# PQS42019_2_v4.net
KiCad netlist of a schematic drawn in EAGLE
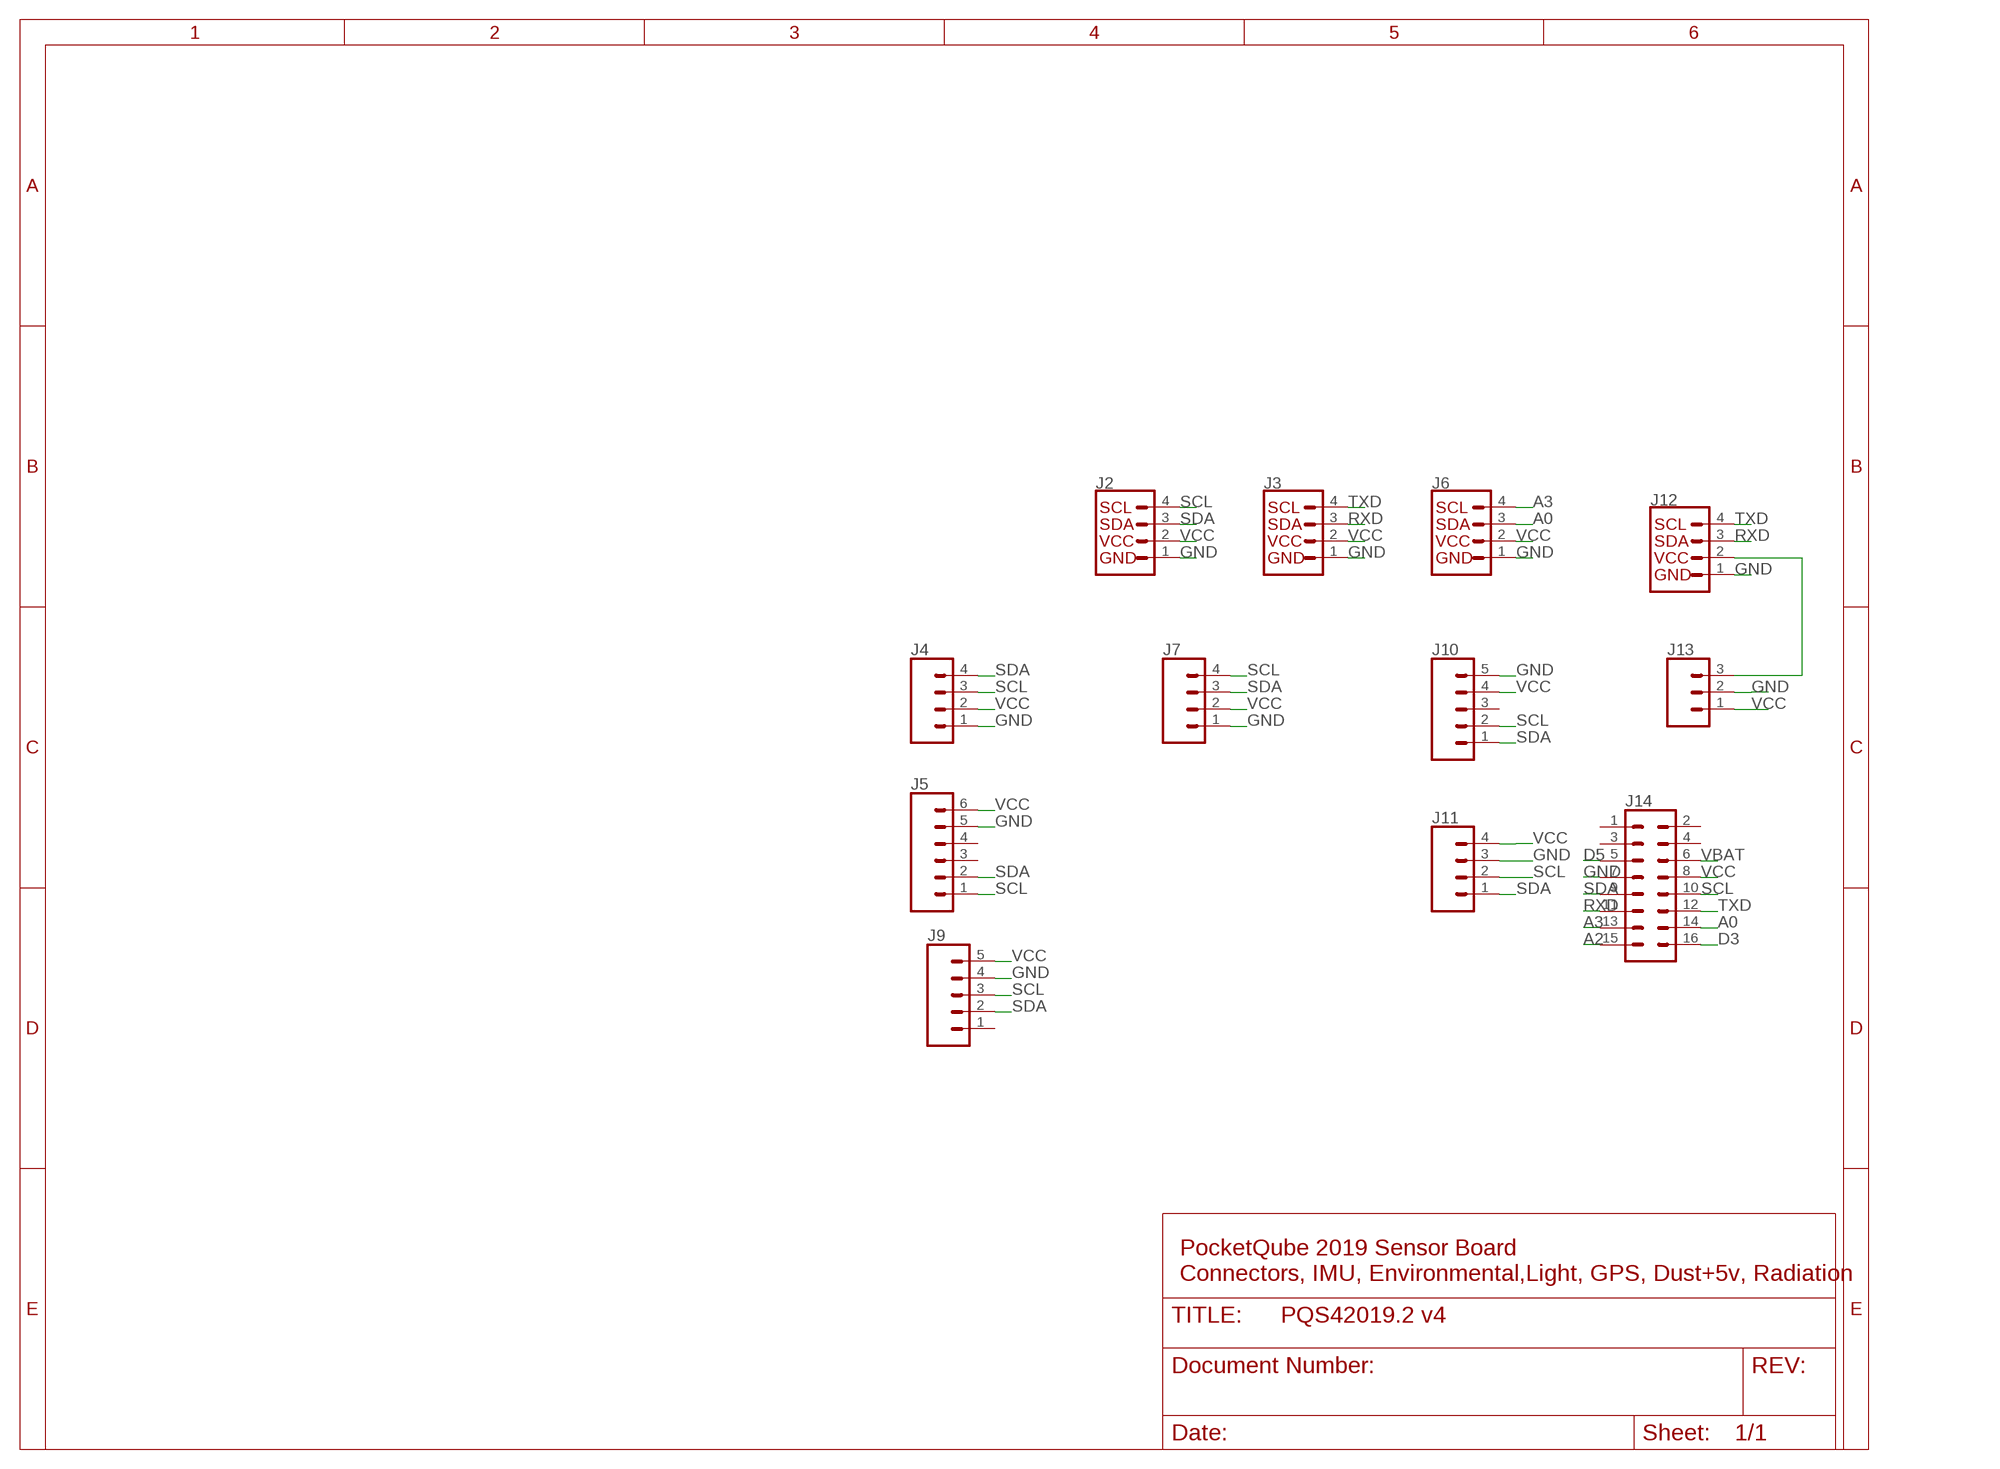
[diagram p0: schematic, sheet 1]

(export (version "E")
  (design (tool "Eeschema 10.0.6"))
  (components
    (comp (ref "J2")
      (value "QWIIC_CONNECTORJS-1MM")
      (footprint "eagle-import:1X04_1MM_RA")
      (libsource (lib "eagle-import") (part "QWIIC_CONNECTORJS-1MM"))
    )
    (comp (ref "J3")
      (value "QWIIC_CONNECTORJS-1MM")
      (footprint "eagle-import:1X04_1MM_RA")
      (libsource (lib "eagle-import") (part "QWIIC_CONNECTORJS-1MM"))
    )
    (comp (ref "J4")
      (value "CONN_04")
      (footprint "eagle-import:1X04")
      (libsource (lib "eagle-import") (part "CONN_04"))
    )
    (comp (ref "J5")
      (value "CONN_06SILK_FEMALE_PTH")
      (footprint "eagle-import:1X06")
      (libsource (lib "eagle-import") (part "CONN_06SILK_FEMALE_PTH"))
    )
    (comp (ref "J6")
      (value "QWIIC_CONNECTORJS-1MM")
      (footprint "eagle-import:1X04_1MM_RA")
      (libsource (lib "eagle-import") (part "QWIIC_CONNECTORJS-1MM"))
    )
    (comp (ref "J7")
      (value "CONN_04")
      (footprint "eagle-import:1X04")
      (libsource (lib "eagle-import") (part "CONN_04"))
    )
    (comp (ref "J9")
      (value "CONN_05")
      (footprint "eagle-import:1X05")
      (libsource (lib "eagle-import") (part "CONN_05"))
    )
    (comp (ref "J10")
      (value "CONN_05")
      (footprint "eagle-import:1X05")
      (libsource (lib "eagle-import") (part "CONN_05"))
    )
    (comp (ref "J11")
      (value "CONN_04")
      (footprint "eagle-import:1X04")
      (libsource (lib "eagle-import") (part "CONN_04"))
    )
    (comp (ref "J12")
      (value "QWIIC_CONNECTORJS-1MM")
      (footprint "eagle-import:1X04_1MM_RA")
      (libsource (lib "eagle-import") (part "QWIIC_CONNECTORJS-1MM"))
    )
    (comp (ref "J13")
      (value "CONN_03")
      (footprint "eagle-import:1X03")
      (libsource (lib "eagle-import") (part "CONN_03"))
    )
    (comp (ref "J14")
      (value "CONN_08X2")
      (footprint "eagle-import:2X8")
      (libsource (lib "eagle-import") (part "CONN_08X2"))
    )
  )
  (nets
    (net (code "1") (name "/A0") (class "Default")
      (node (ref "J14") (pin "14") (pinfunction "14_14") (pintype "passive"))
      (node (ref "J6") (pin "3") (pinfunction "3_3") (pintype "passive"))
    )
    (net (code "2") (name "/A2") (class "Default")
      (node (ref "J14") (pin "15") (pinfunction "15_15") (pintype "passive"))
    )
    (net (code "3") (name "/A3") (class "Default")
      (node (ref "J14") (pin "13") (pinfunction "13_13") (pintype "passive"))
      (node (ref "J6") (pin "4") (pinfunction "4_4") (pintype "passive"))
    )
    (net (code "4") (name "/D3") (class "Default")
      (node (ref "J14") (pin "16") (pinfunction "16_16") (pintype "passive"))
    )
    (net (code "5") (name "/D5") (class "Default")
      (node (ref "J14") (pin "5") (pinfunction "5_5") (pintype "passive"))
    )
    (net (code "6") (name "/GND") (class "Default")
      (node (ref "J10") (pin "5") (pinfunction "5_5") (pintype "passive"))
      (node (ref "J11") (pin "3") (pinfunction "3_3") (pintype "passive"))
      (node (ref "J12") (pin "1") (pinfunction "1_1") (pintype "power_in"))
      (node (ref "J13") (pin "2") (pinfunction "2_2") (pintype "passive"))
      (node (ref "J14") (pin "7") (pinfunction "7_7") (pintype "passive"))
      (node (ref "J2") (pin "1") (pinfunction "1_1") (pintype "power_in"))
      (node (ref "J3") (pin "1") (pinfunction "1_1") (pintype "power_in"))
      (node (ref "J4") (pin "1") (pinfunction "1_1") (pintype "passive"))
      (node (ref "J5") (pin "5") (pinfunction "5_5") (pintype "passive"))
      (node (ref "J6") (pin "1") (pinfunction "1_1") (pintype "power_in"))
      (node (ref "J7") (pin "1") (pinfunction "1_1") (pintype "passive"))
      (node (ref "J9") (pin "4") (pinfunction "4_4") (pintype "passive"))
    )
    (net (code "7") (name "/RXD") (class "Default")
      (node (ref "J12") (pin "3") (pinfunction "3_3") (pintype "passive"))
      (node (ref "J14") (pin "11") (pinfunction "11_11") (pintype "passive"))
      (node (ref "J3") (pin "3") (pinfunction "3_3") (pintype "passive"))
    )
    (net (code "8") (name "/SCL") (class "Default")
      (node (ref "J10") (pin "2") (pinfunction "2_2") (pintype "passive"))
      (node (ref "J11") (pin "2") (pinfunction "2_2") (pintype "passive"))
      (node (ref "J14") (pin "10") (pinfunction "10_10") (pintype "passive"))
      (node (ref "J2") (pin "4") (pinfunction "4_4") (pintype "passive"))
      (node (ref "J4") (pin "3") (pinfunction "3_3") (pintype "passive"))
      (node (ref "J5") (pin "1") (pinfunction "1_1") (pintype "passive"))
      (node (ref "J7") (pin "4") (pinfunction "4_4") (pintype "passive"))
      (node (ref "J9") (pin "3") (pinfunction "3_3") (pintype "passive"))
    )
    (net (code "9") (name "/SDA") (class "Default")
      (node (ref "J10") (pin "1") (pinfunction "1_1") (pintype "passive"))
      (node (ref "J11") (pin "1") (pinfunction "1_1") (pintype "passive"))
      (node (ref "J14") (pin "9") (pinfunction "9_9") (pintype "passive"))
      (node (ref "J2") (pin "3") (pinfunction "3_3") (pintype "passive"))
      (node (ref "J4") (pin "4") (pinfunction "4_4") (pintype "passive"))
      (node (ref "J5") (pin "2") (pinfunction "2_2") (pintype "passive"))
      (node (ref "J7") (pin "3") (pinfunction "3_3") (pintype "passive"))
      (node (ref "J9") (pin "2") (pinfunction "2_2") (pintype "passive"))
    )
    (net (code "10") (name "/TXD") (class "Default")
      (node (ref "J12") (pin "4") (pinfunction "4_4") (pintype "passive"))
      (node (ref "J14") (pin "12") (pinfunction "12_12") (pintype "passive"))
      (node (ref "J3") (pin "4") (pinfunction "4_4") (pintype "passive"))
    )
    (net (code "11") (name "/VBAT") (class "Default")
      (node (ref "J14") (pin "6") (pinfunction "6_6") (pintype "passive"))
    )
    (net (code "12") (name "/VCC") (class "Default")
      (node (ref "J10") (pin "4") (pinfunction "4_4") (pintype "passive"))
      (node (ref "J11") (pin "4") (pinfunction "4_4") (pintype "passive"))
      (node (ref "J13") (pin "1") (pinfunction "1_1") (pintype "passive"))
      (node (ref "J14") (pin "8") (pinfunction "8_8") (pintype "passive"))
      (node (ref "J2") (pin "2") (pinfunction "2_2") (pintype "power_in"))
      (node (ref "J3") (pin "2") (pinfunction "2_2") (pintype "power_in"))
      (node (ref "J4") (pin "2") (pinfunction "2_2") (pintype "passive"))
      (node (ref "J5") (pin "6") (pinfunction "6_6") (pintype "passive"))
      (node (ref "J6") (pin "2") (pinfunction "2_2") (pintype "power_in"))
      (node (ref "J7") (pin "2") (pinfunction "2_2") (pintype "passive"))
      (node (ref "J9") (pin "5") (pinfunction "5_5") (pintype "passive"))
    )
    (net (code "13") (name "Net-(J12-Pad2)") (class "Default")
      (node (ref "J12") (pin "2") (pinfunction "2_2") (pintype "power_in"))
      (node (ref "J13") (pin "3") (pinfunction "3_3") (pintype "passive"))
    )
    (net (code "14") (name "unconnected-(J5-Pad3)") (class "Default")
      (node (ref "J5") (pin "3") (pinfunction "3_3") (pintype "passive"))
    )
    (net (code "15") (name "unconnected-(J5-Pad4)") (class "Default")
      (node (ref "J5") (pin "4") (pinfunction "4_4") (pintype "passive"))
    )
    (net (code "16") (name "unconnected-(J9-Pad1)") (class "Default")
      (node (ref "J9") (pin "1") (pinfunction "1_1") (pintype "passive"))
    )
    (net (code "17") (name "unconnected-(J10-Pad3)") (class "Default")
      (node (ref "J10") (pin "3") (pinfunction "3_3") (pintype "passive"))
    )
    (net (code "18") (name "unconnected-(J14-Pad1)") (class "Default")
      (node (ref "J14") (pin "1") (pinfunction "1_1") (pintype "passive"))
    )
    (net (code "19") (name "unconnected-(J14-Pad2)") (class "Default")
      (node (ref "J14") (pin "2") (pinfunction "2_2") (pintype "passive"))
    )
    (net (code "20") (name "unconnected-(J14-Pad3)") (class "Default")
      (node (ref "J14") (pin "3") (pinfunction "3_3") (pintype "passive"))
    )
    (net (code "21") (name "unconnected-(J14-Pad4)") (class "Default")
      (node (ref "J14") (pin "4") (pinfunction "4_4") (pintype "passive"))
    )
  )
)
